# Output_v1_1.net
KiCad netlist of a schematic drawn in EAGLE
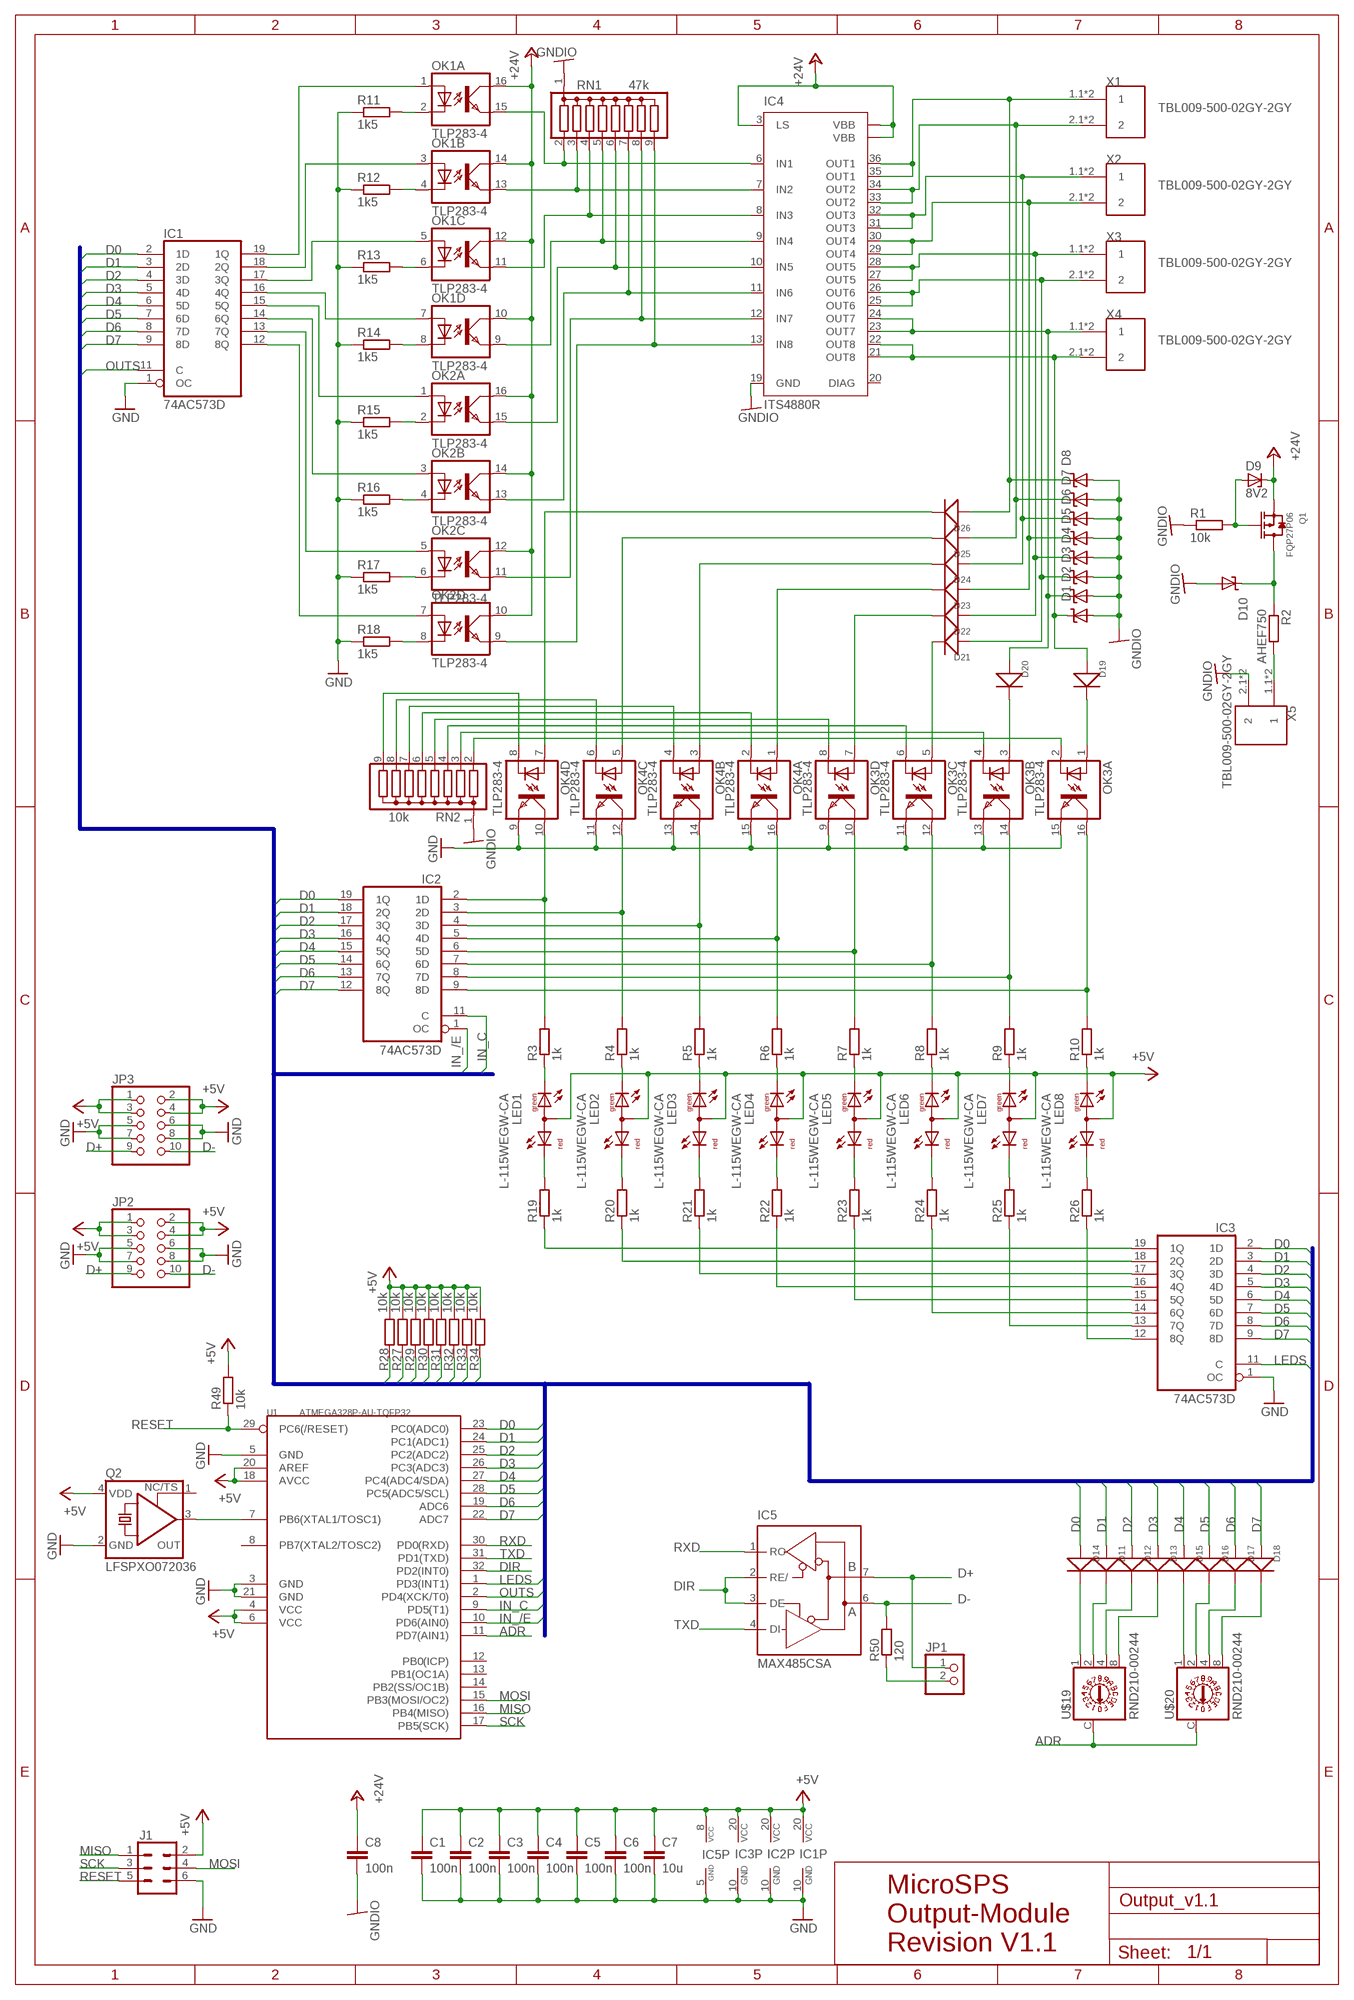
[diagram p0: schematic, sheet 1]

(export (version "E")
  (design (tool "Eeschema 10.0.6"))
  (components
    (comp (ref "C1")
      (value "100n")
      (footprint "eagle-import:C0805")
      (libsource (lib "eagle-import") (part "C-EUC0805"))
    )
    (comp (ref "C2")
      (value "100n")
      (footprint "eagle-import:C0805")
      (libsource (lib "eagle-import") (part "C-EUC0805"))
    )
    (comp (ref "C3")
      (value "100n")
      (footprint "eagle-import:C0805")
      (libsource (lib "eagle-import") (part "C-EUC0805"))
    )
    (comp (ref "C4")
      (value "100n")
      (footprint "eagle-import:C0805")
      (libsource (lib "eagle-import") (part "C-EUC0805"))
    )
    (comp (ref "C5")
      (value "100n")
      (footprint "eagle-import:C0805")
      (libsource (lib "eagle-import") (part "C-EUC0805"))
    )
    (comp (ref "C6")
      (value "100n")
      (footprint "eagle-import:C0805")
      (libsource (lib "eagle-import") (part "C-EUC0805"))
    )
    (comp (ref "C7")
      (value "10u")
      (footprint "eagle-import:C0805")
      (libsource (lib "eagle-import") (part "C-EUC0805"))
    )
    (comp (ref "C8")
      (value "100n")
      (footprint "eagle-import:C0805")
      (libsource (lib "eagle-import") (part "C-EUC0805"))
    )
    (comp (ref "D1")
      (value "SUPPRESSOR-SMBJ")
      (footprint "eagle-import:SMBJ")
      (libsource (lib "eagle-import") (part "SUPPRESSOR-SMBJ"))
    )
    (comp (ref "D2")
      (value "SUPPRESSOR-SMBJ")
      (footprint "eagle-import:SMBJ")
      (libsource (lib "eagle-import") (part "SUPPRESSOR-SMBJ"))
    )
    (comp (ref "D3")
      (value "SUPPRESSOR-SMBJ")
      (footprint "eagle-import:SMBJ")
      (libsource (lib "eagle-import") (part "SUPPRESSOR-SMBJ"))
    )
    (comp (ref "D4")
      (value "SUPPRESSOR-SMBJ")
      (footprint "eagle-import:SMBJ")
      (libsource (lib "eagle-import") (part "SUPPRESSOR-SMBJ"))
    )
    (comp (ref "D5")
      (value "SUPPRESSOR-SMBJ")
      (footprint "eagle-import:SMBJ")
      (libsource (lib "eagle-import") (part "SUPPRESSOR-SMBJ"))
    )
    (comp (ref "D6")
      (value "SUPPRESSOR-SMBJ")
      (footprint "eagle-import:SMBJ")
      (libsource (lib "eagle-import") (part "SUPPRESSOR-SMBJ"))
    )
    (comp (ref "D7")
      (value "SUPPRESSOR-SMBJ")
      (footprint "eagle-import:SMBJ")
      (libsource (lib "eagle-import") (part "SUPPRESSOR-SMBJ"))
    )
    (comp (ref "D8")
      (value "SUPPRESSOR-SMBJ")
      (footprint "eagle-import:SMBJ")
      (libsource (lib "eagle-import") (part "SUPPRESSOR-SMBJ"))
    )
    (comp (ref "D9")
      (value "8V2")
      (footprint "eagle-import:SOD80C")
      (libsource (lib "eagle-import") (part "ZENER-DIODESOD80C"))
    )
    (comp (ref "D10")
      (value "SUPPRESSOR-SMBJ")
      (footprint "eagle-import:SMBJ")
      (libsource (lib "eagle-import") (part "SUPPRESSOR-SMBJ"))
    )
    (comp (ref "D11")
      (value "DIODE'1N4148-SMD'")
      (footprint "eagle-import:LL-34")
      (libsource (lib "eagle-import") (part "DIODE'1N4148-SMD'"))
    )
    (comp (ref "D12")
      (value "DIODE'1N4148-SMD'")
      (footprint "eagle-import:LL-34")
      (libsource (lib "eagle-import") (part "DIODE'1N4148-SMD'"))
    )
    (comp (ref "D13")
      (value "DIODE'1N4148-SMD'")
      (footprint "eagle-import:LL-34")
      (libsource (lib "eagle-import") (part "DIODE'1N4148-SMD'"))
    )
    (comp (ref "D14")
      (value "DIODE'1N4148-SMD'")
      (footprint "eagle-import:LL-34")
      (libsource (lib "eagle-import") (part "DIODE'1N4148-SMD'"))
    )
    (comp (ref "D15")
      (value "DIODE'1N4148-SMD'")
      (footprint "eagle-import:LL-34")
      (libsource (lib "eagle-import") (part "DIODE'1N4148-SMD'"))
    )
    (comp (ref "D16")
      (value "DIODE'1N4148-SMD'")
      (footprint "eagle-import:LL-34")
      (libsource (lib "eagle-import") (part "DIODE'1N4148-SMD'"))
    )
    (comp (ref "D17")
      (value "DIODE'1N4148-SMD'")
      (footprint "eagle-import:LL-34")
      (libsource (lib "eagle-import") (part "DIODE'1N4148-SMD'"))
    )
    (comp (ref "D18")
      (value "DIODE'1N4148-SMD'")
      (footprint "eagle-import:LL-34")
      (libsource (lib "eagle-import") (part "DIODE'1N4148-SMD'"))
    )
    (comp (ref "D19")
      (value "DIODE'1N4148-SMD'")
      (footprint "eagle-import:LL-34")
      (libsource (lib "eagle-import") (part "DIODE'1N4148-SMD'"))
    )
    (comp (ref "D20")
      (value "DIODE'1N4148-SMD'")
      (footprint "eagle-import:LL-34")
      (libsource (lib "eagle-import") (part "DIODE'1N4148-SMD'"))
    )
    (comp (ref "D21")
      (value "DIODE'1N4148-SMD'")
      (footprint "eagle-import:LL-34")
      (libsource (lib "eagle-import") (part "DIODE'1N4148-SMD'"))
    )
    (comp (ref "D22")
      (value "DIODE'1N4148-SMD'")
      (footprint "eagle-import:LL-34")
      (libsource (lib "eagle-import") (part "DIODE'1N4148-SMD'"))
    )
    (comp (ref "D23")
      (value "DIODE'1N4148-SMD'")
      (footprint "eagle-import:LL-34")
      (libsource (lib "eagle-import") (part "DIODE'1N4148-SMD'"))
    )
    (comp (ref "D24")
      (value "DIODE'1N4148-SMD'")
      (footprint "eagle-import:LL-34")
      (libsource (lib "eagle-import") (part "DIODE'1N4148-SMD'"))
    )
    (comp (ref "D25")
      (value "DIODE'1N4148-SMD'")
      (footprint "eagle-import:LL-34")
      (libsource (lib "eagle-import") (part "DIODE'1N4148-SMD'"))
    )
    (comp (ref "D26")
      (value "DIODE'1N4148-SMD'")
      (footprint "eagle-import:LL-34")
      (libsource (lib "eagle-import") (part "DIODE'1N4148-SMD'"))
    )
    (comp (ref "IC1")
      (value "74AC573D")
      (footprint "eagle-import:SO20W")
      (libsource (lib "eagle-import") (part "74573DAC"))
    )
    (comp (ref "IC2")
      (value "74AC573D")
      (footprint "eagle-import:SO20W")
      (libsource (lib "eagle-import") (part "74573DAC"))
    )
    (comp (ref "IC3")
      (value "74AC573D")
      (footprint "eagle-import:SO20W")
      (libsource (lib "eagle-import") (part "74573DAC"))
    )
    (comp (ref "IC4")
      (value "ITS4880R")
      (footprint "eagle-import:PG-DSO-36")
      (libsource (lib "eagle-import") (part "ITS4880R"))
    )
    (comp (ref "IC5")
      (value "MAX485CSA")
      (footprint "eagle-import:SO08")
      (fields (field (name "MF") "MAXIM") (field (name "MPN") "MAX481CSA"))
      (libsource (lib "eagle-import") (part "MAX481CSA"))
    )
    (comp (ref "J1")
      (value "CONN_03X2FEMALE_SMD")
      (footprint "eagle-import:2X3_SMD")
      (libsource (lib "eagle-import") (part "CONN_03X2FEMALE_SMD"))
    )
    (comp (ref "JP1")
      (value "PINHD-1X2")
      (footprint "eagle-import:1X02")
      (libsource (lib "eagle-import") (part "PINHD-1X2"))
    )
    (comp (ref "JP2")
      (value "PINHD-2X5/90")
      (footprint "eagle-import:2X05_90")
      (libsource (lib "eagle-import") (part "PINHD-2X5/90"))
    )
    (comp (ref "JP3")
      (value "PINHD-2X5/90")
      (footprint "eagle-import:2X05_90")
      (libsource (lib "eagle-import") (part "PINHD-2X5/90"))
    )
    (comp (ref "LED1")
      (value "L-115WEGW-CA")
      (footprint "eagle-import:DUOLED-A-3MM")
      (libsource (lib "eagle-import") (part "L-115WEGW-CA"))
    )
    (comp (ref "LED2")
      (value "L-115WEGW-CA")
      (footprint "eagle-import:DUOLED-A-3MM")
      (libsource (lib "eagle-import") (part "L-115WEGW-CA"))
    )
    (comp (ref "LED3")
      (value "L-115WEGW-CA")
      (footprint "eagle-import:DUOLED-A-3MM")
      (libsource (lib "eagle-import") (part "L-115WEGW-CA"))
    )
    (comp (ref "LED4")
      (value "L-115WEGW-CA")
      (footprint "eagle-import:DUOLED-A-3MM")
      (libsource (lib "eagle-import") (part "L-115WEGW-CA"))
    )
    (comp (ref "LED5")
      (value "L-115WEGW-CA")
      (footprint "eagle-import:DUOLED-A-3MM")
      (libsource (lib "eagle-import") (part "L-115WEGW-CA"))
    )
    (comp (ref "LED6")
      (value "L-115WEGW-CA")
      (footprint "eagle-import:DUOLED-A-3MM")
      (libsource (lib "eagle-import") (part "L-115WEGW-CA"))
    )
    (comp (ref "LED7")
      (value "L-115WEGW-CA")
      (footprint "eagle-import:DUOLED-A-3MM")
      (libsource (lib "eagle-import") (part "L-115WEGW-CA"))
    )
    (comp (ref "LED8")
      (value "L-115WEGW-CA")
      (footprint "eagle-import:DUOLED-A-3MM")
      (libsource (lib "eagle-import") (part "L-115WEGW-CA"))
    )
    (comp (ref "OK1")
      (value "TLP283-4")
      (footprint "eagle-import:MINI-FLAT-16")
      (libsource (lib "eagle-import") (part "TLP283-4"))
    )
    (comp (ref "OK2")
      (value "TLP283-4")
      (footprint "eagle-import:MINI-FLAT-16")
      (libsource (lib "eagle-import") (part "TLP283-4"))
    )
    (comp (ref "OK3")
      (value "TLP283-4")
      (footprint "eagle-import:MINI-FLAT-16")
      (libsource (lib "eagle-import") (part "TLP283-4"))
    )
    (comp (ref "OK4")
      (value "TLP283-4")
      (footprint "eagle-import:MINI-FLAT-16")
      (libsource (lib "eagle-import") (part "TLP283-4"))
    )
    (comp (ref "Q1")
      (value "FQP27P06")
      (footprint "eagle-import:TO-220V")
      (libsource (lib "eagle-import") (part "DIP-MOSFET-P-CH-60V-27A-FQP27P06(TO-220)TO-220V"))
    )
    (comp (ref "Q2")
      (value "LFSPXO072036")
      (footprint "eagle-import:5.0X3.2_KXO-56")
      (libsource (lib "eagle-import") (part "KXO-PXO/XO-56-56"))
    )
    (comp (ref "R1")
      (value "10k")
      (footprint "eagle-import:R0805")
      (libsource (lib "eagle-import") (part "R-EU_R0805"))
    )
    (comp (ref "R2")
      (value "AHEF750")
      (footprint "eagle-import:0204_7")
      (libsource (lib "eagle-import") (part "resistor_R-EU_0204/7"))
    )
    (comp (ref "R3")
      (value "1k")
      (footprint "eagle-import:R0805")
      (libsource (lib "eagle-import") (part "R-EU_R0805"))
    )
    (comp (ref "R4")
      (value "1k")
      (footprint "eagle-import:R0805")
      (libsource (lib "eagle-import") (part "R-EU_R0805"))
    )
    (comp (ref "R5")
      (value "1k")
      (footprint "eagle-import:R0805")
      (libsource (lib "eagle-import") (part "R-EU_R0805"))
    )
    (comp (ref "R6")
      (value "1k")
      (footprint "eagle-import:R0805")
      (libsource (lib "eagle-import") (part "R-EU_R0805"))
    )
    (comp (ref "R7")
      (value "1k")
      (footprint "eagle-import:R0805")
      (libsource (lib "eagle-import") (part "R-EU_R0805"))
    )
    (comp (ref "R8")
      (value "1k")
      (footprint "eagle-import:R0805")
      (libsource (lib "eagle-import") (part "R-EU_R0805"))
    )
    (comp (ref "R9")
      (value "1k")
      (footprint "eagle-import:R0805")
      (libsource (lib "eagle-import") (part "R-EU_R0805"))
    )
    (comp (ref "R10")
      (value "1k")
      (footprint "eagle-import:R0805")
      (libsource (lib "eagle-import") (part "R-EU_R0805"))
    )
    (comp (ref "R11")
      (value "1k5")
      (footprint "eagle-import:R0805")
      (libsource (lib "eagle-import") (part "R-EU_R0805"))
    )
    (comp (ref "R12")
      (value "1k5")
      (footprint "eagle-import:R0805")
      (libsource (lib "eagle-import") (part "R-EU_R0805"))
    )
    (comp (ref "R13")
      (value "1k5")
      (footprint "eagle-import:R0805")
      (libsource (lib "eagle-import") (part "R-EU_R0805"))
    )
    (comp (ref "R14")
      (value "1k5")
      (footprint "eagle-import:R0805")
      (libsource (lib "eagle-import") (part "R-EU_R0805"))
    )
    (comp (ref "R15")
      (value "1k5")
      (footprint "eagle-import:R0805")
      (libsource (lib "eagle-import") (part "R-EU_R0805"))
    )
    (comp (ref "R16")
      (value "1k5")
      (footprint "eagle-import:R0805")
      (libsource (lib "eagle-import") (part "R-EU_R0805"))
    )
    (comp (ref "R17")
      (value "1k5")
      (footprint "eagle-import:R0805")
      (libsource (lib "eagle-import") (part "R-EU_R0805"))
    )
    (comp (ref "R18")
      (value "1k5")
      (footprint "eagle-import:R0805")
      (libsource (lib "eagle-import") (part "R-EU_R0805"))
    )
    (comp (ref "R19")
      (value "1k")
      (footprint "eagle-import:R0805")
      (libsource (lib "eagle-import") (part "R-EU_R0805"))
    )
    (comp (ref "R20")
      (value "1k")
      (footprint "eagle-import:R0805")
      (libsource (lib "eagle-import") (part "R-EU_R0805"))
    )
    (comp (ref "R21")
      (value "1k")
      (footprint "eagle-import:R0805")
      (libsource (lib "eagle-import") (part "R-EU_R0805"))
    )
    (comp (ref "R22")
      (value "1k")
      (footprint "eagle-import:R0805")
      (libsource (lib "eagle-import") (part "R-EU_R0805"))
    )
    (comp (ref "R23")
      (value "1k")
      (footprint "eagle-import:R0805")
      (libsource (lib "eagle-import") (part "R-EU_R0805"))
    )
    (comp (ref "R24")
      (value "1k")
      (footprint "eagle-import:R0805")
      (libsource (lib "eagle-import") (part "R-EU_R0805"))
    )
    (comp (ref "R25")
      (value "1k")
      (footprint "eagle-import:R0805")
      (libsource (lib "eagle-import") (part "R-EU_R0805"))
    )
    (comp (ref "R26")
      (value "1k")
      (footprint "eagle-import:R0805")
      (libsource (lib "eagle-import") (part "R-EU_R0805"))
    )
    (comp (ref "R27")
      (value "10k")
      (footprint "eagle-import:R0805")
      (libsource (lib "eagle-import") (part "R-EU_R0805"))
    )
    (comp (ref "R28")
      (value "10k")
      (footprint "eagle-import:R0805")
      (libsource (lib "eagle-import") (part "R-EU_R0805"))
    )
    (comp (ref "R29")
      (value "10k")
      (footprint "eagle-import:R0805")
      (libsource (lib "eagle-import") (part "R-EU_R0805"))
    )
    (comp (ref "R30")
      (value "10k")
      (footprint "eagle-import:R0805")
      (libsource (lib "eagle-import") (part "R-EU_R0805"))
    )
    (comp (ref "R31")
      (value "10k")
      (footprint "eagle-import:R0805")
      (libsource (lib "eagle-import") (part "R-EU_R0805"))
    )
    (comp (ref "R32")
      (value "10k")
      (footprint "eagle-import:R0805")
      (libsource (lib "eagle-import") (part "R-EU_R0805"))
    )
    (comp (ref "R33")
      (value "10k")
      (footprint "eagle-import:R0805")
      (libsource (lib "eagle-import") (part "R-EU_R0805"))
    )
    (comp (ref "R34")
      (value "10k")
      (footprint "eagle-import:R0805")
      (libsource (lib "eagle-import") (part "R-EU_R0805"))
    )
    (comp (ref "R49")
      (value "10k")
      (footprint "eagle-import:R0805")
      (libsource (lib "eagle-import") (part "R-EU_R0805"))
    )
    (comp (ref "R50")
      (value "120")
      (footprint "eagle-import:R0805")
      (libsource (lib "eagle-import") (part "R-EU_R0805"))
    )
    (comp (ref "RN1")
      (value "47k")
      (footprint "eagle-import:SIL9")
      (libsource (lib "eagle-import") (part "G08R"))
    )
    (comp (ref "RN2")
      (value "10k")
      (footprint "eagle-import:SIL9")
      (libsource (lib "eagle-import") (part "G08R"))
    )
    (comp (ref "U$19")
      (value "RND210-00244")
      (footprint "eagle-import:RND210-00244")
      (libsource (lib "eagle-import") (part "RND210-00244"))
    )
    (comp (ref "U$20")
      (value "RND210-00244")
      (footprint "eagle-import:RND210-00244")
      (libsource (lib "eagle-import") (part "RND210-00244"))
    )
    (comp (ref "U1")
      (value "ATMEGA328P-AU-TQFP32")
      (footprint "eagle-import:TQFP32-0.8-7X7MM")
      (fields (field (name "MPN") "ATMEGA328P-AU"))
      (libsource (lib "eagle-import") (part "MCU-ATMEGA328P-AU(TQFP32)"))
    )
    (comp (ref "X1")
      (value "TBL009-500-02GY-2GY")
      (footprint "eagle-import:TBL009-500-02GY-2GY")
      (libsource (lib "eagle-import") (part "TBL009-500-02GY-2GY"))
    )
    (comp (ref "X2")
      (value "TBL009-500-02GY-2GY")
      (footprint "eagle-import:TBL009-500-02GY-2GY")
      (libsource (lib "eagle-import") (part "TBL009-500-02GY-2GY"))
    )
    (comp (ref "X3")
      (value "TBL009-500-02GY-2GY")
      (footprint "eagle-import:TBL009-500-02GY-2GY")
      (libsource (lib "eagle-import") (part "TBL009-500-02GY-2GY"))
    )
    (comp (ref "X4")
      (value "TBL009-500-02GY-2GY")
      (footprint "eagle-import:TBL009-500-02GY-2GY")
      (libsource (lib "eagle-import") (part "TBL009-500-02GY-2GY"))
    )
    (comp (ref "X5")
      (value "TBL009-500-02GY-2GY")
      (footprint "eagle-import:TBL009-500-02GY-2GY")
      (libsource (lib "eagle-import") (part "TBL009-500-02GY-2GY"))
    )
  )
  (nets
    (net (code "1") (name "+5V") (class "Default")
      (node (ref "C1") (pin "1") (pinfunction "1_1") (pintype "passive"))
      (node (ref "C2") (pin "1") (pinfunction "1_1") (pintype "passive"))
      (node (ref "C3") (pin "1") (pinfunction "1_1") (pintype "passive"))
      (node (ref "C4") (pin "1") (pinfunction "1_1") (pintype "passive"))
      (node (ref "C5") (pin "1") (pinfunction "1_1") (pintype "passive"))
      (node (ref "C6") (pin "1") (pinfunction "1_1") (pintype "passive"))
      (node (ref "C7") (pin "1") (pinfunction "1_1") (pintype "passive"))
      (node (ref "IC1") (pin "20") (pinfunction "VCC_20") (pintype "power_in"))
      (node (ref "IC2") (pin "20") (pinfunction "VCC_20") (pintype "power_in"))
      (node (ref "IC3") (pin "20") (pinfunction "VCC_20") (pintype "power_in"))
      (node (ref "IC5") (pin "8") (pinfunction "VCC_8") (pintype "power_in"))
      (node (ref "J1") (pin "2") (pinfunction "2_2") (pintype "bidirectional"))
      (node (ref "JP2") (pin "1") (pinfunction "1_1") (pintype "passive"))
      (node (ref "JP2") (pin "2") (pinfunction "2_2") (pintype "passive"))
      (node (ref "JP2") (pin "3") (pinfunction "3_3") (pintype "passive"))
      (node (ref "JP2") (pin "4") (pinfunction "4_4") (pintype "passive"))
      (node (ref "JP3") (pin "1") (pinfunction "1_1") (pintype "passive"))
      (node (ref "JP3") (pin "2") (pinfunction "2_2") (pintype "passive"))
      (node (ref "JP3") (pin "3") (pinfunction "3_3") (pintype "passive"))
      (node (ref "JP3") (pin "4") (pinfunction "4_4") (pintype "passive"))
      (node (ref "LED1") (pin "2") (pinfunction "A_2") (pintype "passive"))
      (node (ref "LED2") (pin "2") (pinfunction "A_2") (pintype "passive"))
      (node (ref "LED3") (pin "2") (pinfunction "A_2") (pintype "passive"))
      (node (ref "LED4") (pin "2") (pinfunction "A_2") (pintype "passive"))
      (node (ref "LED5") (pin "2") (pinfunction "A_2") (pintype "passive"))
      (node (ref "LED6") (pin "2") (pinfunction "A_2") (pintype "passive"))
      (node (ref "LED7") (pin "2") (pinfunction "A_2") (pintype "passive"))
      (node (ref "LED8") (pin "2") (pinfunction "A_2") (pintype "passive"))
      (node (ref "Q2") (pin "4") (pinfunction "VDD_4") (pintype "power_in"))
      (node (ref "R27") (pin "2") (pinfunction "2_2") (pintype "passive"))
      (node (ref "R28") (pin "2") (pinfunction "2_2") (pintype "passive"))
      (node (ref "R29") (pin "2") (pinfunction "2_2") (pintype "passive"))
      (node (ref "R30") (pin "2") (pinfunction "2_2") (pintype "passive"))
      (node (ref "R31") (pin "2") (pinfunction "2_2") (pintype "passive"))
      (node (ref "R32") (pin "2") (pinfunction "2_2") (pintype "passive"))
      (node (ref "R33") (pin "2") (pinfunction "2_2") (pintype "passive"))
      (node (ref "R34") (pin "2") (pinfunction "2_2") (pintype "passive"))
      (node (ref "R49") (pin "2") (pinfunction "2_2") (pintype "passive"))
      (node (ref "U1") (pin "18") (pinfunction "AVCC_18") (pintype "bidirectional"))
      (node (ref "U1") (pin "20") (pinfunction "AREF_20") (pintype "bidirectional"))
      (node (ref "U1") (pin "4") (pinfunction "VCC_4") (pintype "bidirectional"))
      (node (ref "U1") (pin "6") (pinfunction "VCC_6") (pintype "bidirectional"))
    )
    (net (code "2") (name "+24V") (class "Default")
      (node (ref "C8") (pin "1") (pinfunction "1_1") (pintype "passive"))
      (node (ref "D9") (pin "C") (pinfunction "C_C") (pintype "passive"))
      (node (ref "IC4") (pin "3") (pinfunction "LS_3") (pintype "input"))
      (node (ref "IC4") (pin "TH@1") (pinfunction "VBB_TH@1") (pintype "input"))
      (node (ref "IC4") (pin "TH@2") (pinfunction "VBB_TH@2") (pintype "input"))
      (node (ref "OK1") (pin "10") (pinfunction "COL_10") (pintype "passive"))
      (node (ref "OK1") (pin "12") (pinfunction "COL_12") (pintype "passive"))
      (node (ref "OK1") (pin "14") (pinfunction "COL_14") (pintype "passive"))
      (node (ref "OK1") (pin "16") (pinfunction "COL_16") (pintype "passive"))
      (node (ref "OK2") (pin "10") (pinfunction "COL_10") (pintype "passive"))
      (node (ref "OK2") (pin "12") (pinfunction "COL_12") (pintype "passive"))
      (node (ref "OK2") (pin "14") (pinfunction "COL_14") (pintype "passive"))
      (node (ref "OK2") (pin "16") (pinfunction "COL_16") (pintype "passive"))
      (node (ref "Q1") (pin "3") (pinfunction "S_3") (pintype "passive"))
    )
    (net (code "3") (name "/ADR") (class "Default")
      (node (ref "U$19") (pin "C") (pinfunction "C_C") (pintype "passive"))
      (node (ref "U$20") (pin "C") (pinfunction "C_C") (pintype "passive"))
      (node (ref "U1") (pin "11") (pinfunction "PD7(AIN1)_11") (pintype "bidirectional"))
    )
    (net (code "4") (name "/D+") (class "Default")
      (node (ref "IC5") (pin "7") (pinfunction "B_7") (pintype "passive"))
      (node (ref "JP1") (pin "1") (pinfunction "1_1") (pintype "passive"))
      (node (ref "JP2") (pin "9") (pinfunction "9_9") (pintype "passive"))
      (node (ref "JP3") (pin "9") (pinfunction "9_9") (pintype "passive"))
    )
    (net (code "5") (name "/D-") (class "Default")
      (node (ref "IC5") (pin "6") (pinfunction "A_6") (pintype "passive"))
      (node (ref "JP2") (pin "10") (pinfunction "10_10") (pintype "passive"))
      (node (ref "JP3") (pin "10") (pinfunction "10_10") (pintype "passive"))
      (node (ref "R50") (pin "2") (pinfunction "2_2") (pintype "passive"))
    )
    (net (code "6") (name "/D0") (class "Default")
      (node (ref "D14") (pin "A") (pinfunction "+_A") (pintype "passive"))
      (node (ref "IC1") (pin "2") (pinfunction "1D_2") (pintype "input"))
      (node (ref "IC2") (pin "19") (pinfunction "1Q_19") (pintype "tri_state"))
      (node (ref "IC3") (pin "2") (pinfunction "1D_2") (pintype "input"))
      (node (ref "R28") (pin "1") (pinfunction "1_1") (pintype "passive"))
      (node (ref "U1") (pin "23") (pinfunction "PC0(ADC0)_23") (pintype "bidirectional"))
    )
    (net (code "7") (name "/D1") (class "Default")
      (node (ref "D11") (pin "A") (pinfunction "+_A") (pintype "passive"))
      (node (ref "IC1") (pin "3") (pinfunction "2D_3") (pintype "input"))
      (node (ref "IC2") (pin "18") (pinfunction "2Q_18") (pintype "tri_state"))
      (node (ref "IC3") (pin "3") (pinfunction "2D_3") (pintype "input"))
      (node (ref "R27") (pin "1") (pinfunction "1_1") (pintype "passive"))
      (node (ref "U1") (pin "24") (pinfunction "PC1(ADC1)_24") (pintype "bidirectional"))
    )
    (net (code "8") (name "/D2") (class "Default")
      (node (ref "D12") (pin "A") (pinfunction "+_A") (pintype "passive"))
      (node (ref "IC1") (pin "4") (pinfunction "3D_4") (pintype "input"))
      (node (ref "IC2") (pin "17") (pinfunction "3Q_17") (pintype "tri_state"))
      (node (ref "IC3") (pin "4") (pinfunction "3D_4") (pintype "input"))
      (node (ref "R29") (pin "1") (pinfunction "1_1") (pintype "passive"))
      (node (ref "U1") (pin "25") (pinfunction "PC2(ADC2)_25") (pintype "bidirectional"))
    )
    (net (code "9") (name "/D3") (class "Default")
      (node (ref "D13") (pin "A") (pinfunction "+_A") (pintype "passive"))
      (node (ref "IC1") (pin "5") (pinfunction "4D_5") (pintype "input"))
      (node (ref "IC2") (pin "16") (pinfunction "4Q_16") (pintype "tri_state"))
      (node (ref "IC3") (pin "5") (pinfunction "4D_5") (pintype "input"))
      (node (ref "R30") (pin "1") (pinfunction "1_1") (pintype "passive"))
      (node (ref "U1") (pin "26") (pinfunction "PC3(ADC3)_26") (pintype "bidirectional"))
    )
    (net (code "10") (name "/D4") (class "Default")
      (node (ref "D15") (pin "A") (pinfunction "+_A") (pintype "passive"))
      (node (ref "IC1") (pin "6") (pinfunction "5D_6") (pintype "input"))
      (node (ref "IC2") (pin "15") (pinfunction "5Q_15") (pintype "tri_state"))
      (node (ref "IC3") (pin "6") (pinfunction "5D_6") (pintype "input"))
      (node (ref "R31") (pin "1") (pinfunction "1_1") (pintype "passive"))
      (node (ref "U1") (pin "27") (pinfunction "PC4(ADC4/SDA)_27") (pintype "bidirectional"))
    )
    (net (code "11") (name "/D5") (class "Default")
      (node (ref "D16") (pin "A") (pinfunction "+_A") (pintype "passive"))
      (node (ref "IC1") (pin "7") (pinfunction "6D_7") (pintype "input"))
      (node (ref "IC2") (pin "14") (pinfunction "6Q_14") (pintype "tri_state"))
      (node (ref "IC3") (pin "7") (pinfunction "6D_7") (pintype "input"))
      (node (ref "R32") (pin "1") (pinfunction "1_1") (pintype "passive"))
      (node (ref "U1") (pin "28") (pinfunction "PC5(ADC5/SCL)_28") (pintype "bidirectional"))
    )
    (net (code "12") (name "/D6") (class "Default")
      (node (ref "D17") (pin "A") (pinfunction "+_A") (pintype "passive"))
      (node (ref "IC1") (pin "8") (pinfunction "7D_8") (pintype "input"))
      (node (ref "IC2") (pin "13") (pinfunction "7Q_13") (pintype "tri_state"))
      (node (ref "IC3") (pin "8") (pinfunction "7D_8") (pintype "input"))
      (node (ref "R33") (pin "1") (pinfunction "1_1") (pintype "passive"))
      (node (ref "U1") (pin "19") (pinfunction "ADC6_19") (pintype "bidirectional"))
    )
    (net (code "13") (name "/D7") (class "Default")
      (node (ref "D18") (pin "A") (pinfunction "+_A") (pintype "passive"))
      (node (ref "IC1") (pin "9") (pinfunction "8D_9") (pintype "input"))
      (node (ref "IC2") (pin "12") (pinfunction "8Q_12") (pintype "tri_state"))
      (node (ref "IC3") (pin "9") (pinfunction "8D_9") (pintype "input"))
      (node (ref "R34") (pin "1") (pinfunction "1_1") (pintype "passive"))
      (node (ref "U1") (pin "22") (pinfunction "ADC7_22") (pintype "bidirectional"))
    )
    (net (code "14") (name "/DIR") (class "Default")
      (node (ref "IC5") (pin "2") (pinfunction "RE/_2") (pintype "input"))
      (node (ref "IC5") (pin "3") (pinfunction "DE_3") (pintype "input"))
      (node (ref "U1") (pin "32") (pinfunction "PD2(INT0)_32") (pintype "bidirectional"))
    )
    (net (code "15") (name "/IN_C") (class "Default")
      (node (ref "IC2") (pin "11") (pinfunction "C_11") (pintype "input"))
      (node (ref "U1") (pin "9") (pinfunction "PD5(T1)_9") (pintype "bidirectional"))
    )
    (net (code "16") (name "/IN_{slash}E") (class "Default")
      (node (ref "IC2") (pin "1") (pinfunction "OC_1") (pintype "input"))
      (node (ref "U1") (pin "10") (pinfunction "PD6(AIN0)_10") (pintype "bidirectional"))
    )
    (net (code "17") (name "/LEDS") (class "Default")
      (node (ref "IC3") (pin "11") (pinfunction "C_11") (pintype "input"))
      (node (ref "U1") (pin "1") (pinfunction "PD3(INT1)_1") (pintype "bidirectional"))
    )
    (net (code "18") (name "/MISO") (class "Default")
      (node (ref "J1") (pin "1") (pinfunction "1_1") (pintype "bidirectional"))
      (node (ref "U1") (pin "16") (pinfunction "PB4(MISO)_16") (pintype "bidirectional"))
    )
    (net (code "19") (name "/MOSI") (class "Default")
      (node (ref "J1") (pin "4") (pinfunction "4_4") (pintype "bidirectional"))
      (node (ref "U1") (pin "15") (pinfunction "PB3(MOSI/OC2)_15") (pintype "bidirectional"))
    )
    (net (code "20") (name "/OUTS") (class "Default")
      (node (ref "IC1") (pin "11") (pinfunction "C_11") (pintype "input"))
      (node (ref "U1") (pin "2") (pinfunction "PD4(XCK/T0)_2") (pintype "bidirectional"))
    )
    (net (code "21") (name "/RESET") (class "Default")
      (node (ref "J1") (pin "5") (pinfunction "5_5") (pintype "bidirectional"))
      (node (ref "R49") (pin "1") (pinfunction "1_1") (pintype "passive"))
      (node (ref "U1") (pin "29") (pinfunction "PC6(/RESET)_29") (pintype "bidirectional"))
    )
    (net (code "22") (name "/RXD") (class "Default")
      (node (ref "IC5") (pin "1") (pinfunction "RO_1") (pintype "output"))
      (node (ref "U1") (pin "30") (pinfunction "PD0(RXD)_30") (pintype "bidirectional"))
    )
    (net (code "23") (name "/SCK") (class "Default")
      (node (ref "J1") (pin "3") (pinfunction "3_3") (pintype "bidirectional"))
      (node (ref "U1") (pin "17") (pinfunction "PB5(SCK)_17") (pintype "bidirectional"))
    )
    (net (code "24") (name "/TXD") (class "Default")
      (node (ref "IC5") (pin "4") (pinfunction "DI_4") (pintype "input"))
      (node (ref "U1") (pin "31") (pinfunction "PD1(TXD)_31") (pintype "bidirectional"))
    )
    (net (code "25") (name "GND") (class "Default")
      (node (ref "C1") (pin "2") (pinfunction "2_2") (pintype "passive"))
      (node (ref "C2") (pin "2") (pinfunction "2_2") (pintype "passive"))
      (node (ref "C3") (pin "2") (pinfunction "2_2") (pintype "passive"))
      (node (ref "C4") (pin "2") (pinfunction "2_2") (pintype "passive"))
      (node (ref "C5") (pin "2") (pinfunction "2_2") (pintype "passive"))
      (node (ref "C6") (pin "2") (pinfunction "2_2") (pintype "passive"))
      (node (ref "C7") (pin "2") (pinfunction "2_2") (pintype "passive"))
      (node (ref "IC1") (pin "1") (pinfunction "OC_1") (pintype "input"))
      (node (ref "IC1") (pin "10") (pinfunction "GND_10") (pintype "power_in"))
      (node (ref "IC2") (pin "10") (pinfunction "GND_10") (pintype "power_in"))
      (node (ref "IC3") (pin "1") (pinfunction "OC_1") (pintype "input"))
      (node (ref "IC3") (pin "10") (pinfunction "GND_10") (pintype "power_in"))
      (node (ref "IC5") (pin "5") (pinfunction "GND_5") (pintype "power_in"))
      (node (ref "J1") (pin "6") (pinfunction "6_6") (pintype "bidirectional"))
      (node (ref "JP2") (pin "5") (pinfunction "5_5") (pintype "passive"))
      (node (ref "JP2") (pin "6") (pinfunction "6_6") (pintype "passive"))
      (node (ref "JP2") (pin "7") (pinfunction "7_7") (pintype "passive"))
      (node (ref "JP2") (pin "8") (pinfunction "8_8") (pintype "passive"))
      (node (ref "JP3") (pin "5") (pinfunction "5_5") (pintype "passive"))
      (node (ref "JP3") (pin "6") (pinfunction "6_6") (pintype "passive"))
      (node (ref "JP3") (pin "7") (pinfunction "7_7") (pintype "passive"))
      (node (ref "JP3") (pin "8") (pinfunction "8_8") (pintype "passive"))
      (node (ref "OK3") (pin "11") (pinfunction "EMIT_11") (pintype "passive"))
      (node (ref "OK3") (pin "13") (pinfunction "EMIT_13") (pintype "passive"))
      (node (ref "OK3") (pin "15") (pinfunction "EMIT_15") (pintype "passive"))
      (node (ref "OK3") (pin "9") (pinfunction "EMIT_9") (pintype "passive"))
      (node (ref "OK4") (pin "11") (pinfunction "EMIT_11") (pintype "passive"))
      (node (ref "OK4") (pin "13") (pinfunction "EMIT_13") (pintype "passive"))
      (node (ref "OK4") (pin "15") (pinfunction "EMIT_15") (pintype "passive"))
      (node (ref "OK4") (pin "9") (pinfunction "EMIT_9") (pintype "passive"))
      (node (ref "Q2") (pin "2") (pinfunction "GND_2") (pintype "power_in"))
      (node (ref "R11") (pin "1") (pinfunction "1_1") (pintype "passive"))
      (node (ref "R12") (pin "1") (pinfunction "1_1") (pintype "passive"))
      (node (ref "R13") (pin "1") (pinfunction "1_1") (pintype "passive"))
      (node (ref "R14") (pin "1") (pinfunction "1_1") (pintype "passive"))
      (node (ref "R15") (pin "1") (pinfunction "1_1") (pintype "passive"))
      (node (ref "R16") (pin "1") (pinfunction "1_1") (pintype "passive"))
      (node (ref "R17") (pin "1") (pinfunction "1_1") (pintype "passive"))
      (node (ref "R18") (pin "1") (pinfunction "1_1") (pintype "passive"))
      (node (ref "U1") (pin "21") (pinfunction "GND_21") (pintype "bidirectional"))
      (node (ref "U1") (pin "3") (pinfunction "GND_3") (pintype "bidirectional"))
      (node (ref "U1") (pin "5") (pinfunction "GND_5") (pintype "bidirectional"))
    )
    (net (code "26") (name "GNDIO") (class "Default")
      (node (ref "C8") (pin "2") (pinfunction "2_2") (pintype "passive"))
      (node (ref "D1") (pin "A") (pinfunction "A_A") (pintype "passive"))
      (node (ref "D10") (pin "A") (pinfunction "A_A") (pintype "passive"))
      (node (ref "D2") (pin "A") (pinfunction "A_A") (pintype "passive"))
      (node (ref "D3") (pin "A") (pinfunction "A_A") (pintype "passive"))
      (node (ref "D4") (pin "A") (pinfunction "A_A") (pintype "passive"))
      (node (ref "D5") (pin "A") (pinfunction "A_A") (pintype "passive"))
      (node (ref "D6") (pin "A") (pinfunction "A_A") (pintype "passive"))
      (node (ref "D7") (pin "A") (pinfunction "A_A") (pintype "passive"))
      (node (ref "D8") (pin "A") (pinfunction "A_A") (pintype "passive"))
      (node (ref "IC4") (pin "19") (pinfunction "GND_19") (pintype "power_in"))
      (node (ref "R1") (pin "1") (pinfunction "1_1") (pintype "passive"))
      (node (ref "RN1") (pin "1") (pinfunction "1_1") (pintype "passive"))
      (node (ref "RN2") (pin "1") (pinfunction "1_1") (pintype "passive"))
      (node (ref "X5") (pin "2.1") (pinfunction "2_2.1") (pintype "bidirectional"))
      (node (ref "X5") (pin "2.2") (pinfunction "2_2.2") (pintype "bidirectional"))
    )
    (net (code "27") (name "Net-(D11--)") (class "Default")
      (node (ref "D11") (pin "C") (pinfunction "-_C") (pintype "passive"))
      (node (ref "U$19") (pin "2") (pinfunction "2_2") (pintype "passive"))
    )
    (net (code "28") (name "Net-(D12--)") (class "Default")
      (node (ref "D12") (pin "C") (pinfunction "-_C") (pintype "passive"))
      (node (ref "U$19") (pin "4") (pinfunction "4_4") (pintype "passive"))
    )
    (net (code "29") (name "Net-(D13--)") (class "Default")
      (node (ref "D13") (pin "C") (pinfunction "-_C") (pintype "passive"))
      (node (ref "U$19") (pin "8") (pinfunction "8_8") (pintype "passive"))
    )
    (net (code "30") (name "Net-(D14--)") (class "Default")
      (node (ref "D14") (pin "C") (pinfunction "-_C") (pintype "passive"))
      (node (ref "U$19") (pin "1") (pinfunction "1_1") (pintype "passive"))
    )
    (net (code "31") (name "Net-(D15--)") (class "Default")
      (node (ref "D15") (pin "C") (pinfunction "-_C") (pintype "passive"))
      (node (ref "U$20") (pin "1") (pinfunction "1_1") (pintype "passive"))
    )
    (net (code "32") (name "Net-(D16--)") (class "Default")
      (node (ref "D16") (pin "C") (pinfunction "-_C") (pintype "passive"))
      (node (ref "U$20") (pin "2") (pinfunction "2_2") (pintype "passive"))
    )
    (net (code "33") (name "Net-(D17--)") (class "Default")
      (node (ref "D17") (pin "C") (pinfunction "-_C") (pintype "passive"))
      (node (ref "U$20") (pin "4") (pinfunction "4_4") (pintype "passive"))
    )
    (net (code "34") (name "Net-(D18--)") (class "Default")
      (node (ref "D18") (pin "C") (pinfunction "-_C") (pintype "passive"))
      (node (ref "U$20") (pin "8") (pinfunction "8_8") (pintype "passive"))
    )
    (net (code "35") (name "Net-(D19-+)") (class "Default")
      (node (ref "D1") (pin "C") (pinfunction "C_C") (pintype "passive"))
      (node (ref "D19") (pin "A") (pinfunction "+_A") (pintype "passive"))
      (node (ref "IC4") (pin "21") (pinfunction "OUT8_21") (pintype "output"))
      (node (ref "IC4") (pin "22") (pinfunction "OUT8_22") (pintype "output"))
      (node (ref "X4") (pin "2.1") (pinfunction "2_2.1") (pintype "bidirectional"))
      (node (ref "X4") (pin "2.2") (pinfunction "2_2.2") (pintype "bidirectional"))
    )
    (net (code "36") (name "Net-(D19--)") (class "Default")
      (node (ref "D19") (pin "C") (pinfunction "-_C") (pintype "passive"))
      (node (ref "OK3") (pin "1") (pinfunction "A_1") (pintype "passive"))
    )
    (net (code "37") (name "Net-(D20-+)") (class "Default")
      (node (ref "D2") (pin "C") (pinfunction "C_C") (pintype "passive"))
      (node (ref "D20") (pin "A") (pinfunction "+_A") (pintype "passive"))
      (node (ref "IC4") (pin "23") (pinfunction "OUT7_23") (pintype "output"))
      (node (ref "IC4") (pin "24") (pinfunction "OUT7_24") (pintype "output"))
      (node (ref "X4") (pin "1.1") (pinfunction "1_1.1") (pintype "bidirectional"))
      (node (ref "X4") (pin "1.2") (pinfunction "1_1.2") (pintype "bidirectional"))
    )
    (net (code "38") (name "Net-(D20--)") (class "Default")
      (node (ref "D20") (pin "C") (pinfunction "-_C") (pintype "passive"))
      (node (ref "OK3") (pin "3") (pinfunction "A_3") (pintype "passive"))
    )
    (net (code "39") (name "Net-(D21-+)") (class "Default")
      (node (ref "D21") (pin "A") (pinfunction "+_A") (pintype "passive"))
      (node (ref "D3") (pin "C") (pinfunction "C_C") (pintype "passive"))
      (node (ref "IC4") (pin "25") (pinfunction "OUT6_25") (pintype "output"))
      (node (ref "IC4") (pin "26") (pinfunction "OUT6_26") (pintype "output"))
      (node (ref "X3") (pin "2.1") (pinfunction "2_2.1") (pintype "bidirectional"))
      (node (ref "X3") (pin "2.2") (pinfunction "2_2.2") (pintype "bidirectional"))
    )
    (net (code "40") (name "Net-(D21--)") (class "Default")
      (node (ref "D21") (pin "C") (pinfunction "-_C") (pintype "passive"))
      (node (ref "OK3") (pin "5") (pinfunction "A_5") (pintype "passive"))
    )
    (net (code "41") (name "Net-(D22-+)") (class "Default")
      (node (ref "D22") (pin "A") (pinfunction "+_A") (pintype "passive"))
      (node (ref "D4") (pin "C") (pinfunction "C_C") (pintype "passive"))
      (node (ref "IC4") (pin "27") (pinfunction "OUT5_27") (pintype "output"))
      (node (ref "IC4") (pin "28") (pinfunction "OUT5_28") (pintype "output"))
      (node (ref "X3") (pin "1.1") (pinfunction "1_1.1") (pintype "bidirectional"))
      (node (ref "X3") (pin "1.2") (pinfunction "1_1.2") (pintype "bidirectional"))
    )
    (net (code "42") (name "Net-(D22--)") (class "Default")
      (node (ref "D22") (pin "C") (pinfunction "-_C") (pintype "passive"))
      (node (ref "OK3") (pin "7") (pinfunction "A_7") (pintype "passive"))
    )
    (net (code "43") (name "Net-(D23-+)") (class "Default")
      (node (ref "D23") (pin "A") (pinfunction "+_A") (pintype "passive"))
      (node (ref "D5") (pin "C") (pinfunction "C_C") (pintype "passive"))
      (node (ref "IC4") (pin "29") (pinfunction "OUT4_29") (pintype "output"))
      (node (ref "IC4") (pin "30") (pinfunction "OUT4_30") (pintype "output"))
      (node (ref "X2") (pin "2.1") (pinfunction "2_2.1") (pintype "bidirectional"))
      (node (ref "X2") (pin "2.2") (pinfunction "2_2.2") (pintype "bidirectional"))
    )
    (net (code "44") (name "Net-(D23--)") (class "Default")
      (node (ref "D23") (pin "C") (pinfunction "-_C") (pintype "passive"))
      (node (ref "OK4") (pin "1") (pinfunction "A_1") (pintype "passive"))
    )
    (net (code "45") (name "Net-(D24-+)") (class "Default")
      (node (ref "D24") (pin "A") (pinfunction "+_A") (pintype "passive"))
      (node (ref "D6") (pin "C") (pinfunction "C_C") (pintype "passive"))
      (node (ref "IC4") (pin "31") (pinfunction "OUT3_31") (pintype "output"))
      (node (ref "IC4") (pin "32") (pinfunction "OUT3_32") (pintype "output"))
      (node (ref "X2") (pin "1.1") (pinfunction "1_1.1") (pintype "bidirectional"))
      (node (ref "X2") (pin "1.2") (pinfunction "1_1.2") (pintype "bidirectional"))
    )
    (net (code "46") (name "Net-(D24--)") (class "Default")
      (node (ref "D24") (pin "C") (pinfunction "-_C") (pintype "passive"))
      (node (ref "OK4") (pin "3") (pinfunction "A_3") (pintype "passive"))
    )
    (net (code "47") (name "Net-(D25-+)") (class "Default")
      (node (ref "D25") (pin "A") (pinfunction "+_A") (pintype "passive"))
      (node (ref "D7") (pin "C") (pinfunction "C_C") (pintype "passive"))
      (node (ref "IC4") (pin "33") (pinfunction "OUT2_33") (pintype "output"))
      (node (ref "IC4") (pin "34") (pinfunction "OUT2_34") (pintype "output"))
      (node (ref "X1") (pin "2.1") (pinfunction "2_2.1") (pintype "bidirectional"))
      (node (ref "X1") (pin "2.2") (pinfunction "2_2.2") (pintype "bidirectional"))
    )
    (net (code "48") (name "Net-(D25--)") (class "Default")
      (node (ref "D25") (pin "C") (pinfunction "-_C") (pintype "passive"))
      (node (ref "OK4") (pin "5") (pinfunction "A_5") (pintype "passive"))
    )
    (net (code "49") (name "Net-(D26-+)") (class "Default")
      (node (ref "D26") (pin "A") (pinfunction "+_A") (pintype "passive"))
      (node (ref "D8") (pin "C") (pinfunction "C_C") (pintype "passive"))
      (node (ref "IC4") (pin "35") (pinfunction "OUT1_35") (pintype "output"))
      (node (ref "IC4") (pin "36") (pinfunction "OUT1_36") (pintype "output"))
      (node (ref "X1") (pin "1.1") (pinfunction "1_1.1") (pintype "bidirectional"))
      (node (ref "X1") (pin "1.2") (pinfunction "1_1.2") (pintype "bidirectional"))
    )
    (net (code "50") (name "Net-(D26--)") (class "Default")
      (node (ref "D26") (pin "C") (pinfunction "-_C") (pintype "passive"))
      (node (ref "OK4") (pin "7") (pinfunction "A_7") (pintype "passive"))
    )
    (net (code "51") (name "Net-(IC1A-1Q)") (class "Default")
      (node (ref "IC1") (pin "19") (pinfunction "1Q_19") (pintype "tri_state"))
      (node (ref "OK1") (pin "1") (pinfunction "A_1") (pintype "passive"))
    )
    (net (code "52") (name "Net-(IC1A-2Q)") (class "Default")
      (node (ref "IC1") (pin "18") (pinfunction "2Q_18") (pintype "tri_state"))
      (node (ref "OK1") (pin "3") (pinfunction "A_3") (pintype "passive"))
    )
    (net (code "53") (name "Net-(IC1A-3Q)") (class "Default")
      (node (ref "IC1") (pin "17") (pinfunction "3Q_17") (pintype "tri_state"))
      (node (ref "OK1") (pin "5") (pinfunction "A_5") (pintype "passive"))
    )
    (net (code "54") (name "Net-(IC1A-4Q)") (class "Default")
      (node (ref "IC1") (pin "16") (pinfunction "4Q_16") (pintype "tri_state"))
      (node (ref "OK1") (pin "7") (pinfunction "A_7") (pintype "passive"))
    )
    (net (code "55") (name "Net-(IC1A-5Q)") (class "Default")
      (node (ref "IC1") (pin "15") (pinfunction "5Q_15") (pintype "tri_state"))
      (node (ref "OK2") (pin "1") (pinfunction "A_1") (pintype "passive"))
    )
    (net (code "56") (name "Net-(IC1A-6Q)") (class "Default")
      (node (ref "IC1") (pin "14") (pinfunction "6Q_14") (pintype "tri_state"))
      (node (ref "OK2") (pin "3") (pinfunction "A_3") (pintype "passive"))
    )
    (net (code "57") (name "Net-(IC1A-7Q)") (class "Default")
      (node (ref "IC1") (pin "13") (pinfunction "7Q_13") (pintype "tri_state"))
      (node (ref "OK2") (pin "5") (pinfunction "A_5") (pintype "passive"))
    )
    (net (code "58") (name "Net-(IC1A-8Q)") (class "Default")
      (node (ref "IC1") (pin "12") (pinfunction "8Q_12") (pintype "tri_state"))
      (node (ref "OK2") (pin "7") (pinfunction "A_7") (pintype "passive"))
    )
    (net (code "59") (name "Net-(IC2A-1D)") (class "Default")
      (node (ref "IC2") (pin "2") (pinfunction "1D_2") (pintype "input"))
      (node (ref "OK4") (pin "10") (pinfunction "COL_10") (pintype "passive"))
      (node (ref "R3") (pin "2") (pinfunction "2_2") (pintype "passive"))
    )
    (net (code "60") (name "Net-(IC2A-2D)") (class "Default")
      (node (ref "IC2") (pin "3") (pinfunction "2D_3") (pintype "input"))
      (node (ref "OK4") (pin "12") (pinfunction "COL_12") (pintype "passive"))
      (node (ref "R4") (pin "2") (pinfunction "2_2") (pintype "passive"))
    )
    (net (code "61") (name "Net-(IC2A-3D)") (class "Default")
      (node (ref "IC2") (pin "4") (pinfunction "3D_4") (pintype "input"))
      (node (ref "OK4") (pin "14") (pinfunction "COL_14") (pintype "passive"))
      (node (ref "R5") (pin "2") (pinfunction "2_2") (pintype "passive"))
    )
    (net (code "62") (name "Net-(IC2A-4D)") (class "Default")
      (node (ref "IC2") (pin "5") (pinfunction "4D_5") (pintype "input"))
      (node (ref "OK4") (pin "16") (pinfunction "COL_16") (pintype "passive"))
      (node (ref "R6") (pin "2") (pinfunction "2_2") (pintype "passive"))
    )
    (net (code "63") (name "Net-(IC2A-5D)") (class "Default")
      (node (ref "IC2") (pin "6") (pinfunction "5D_6") (pintype "input"))
      (node (ref "OK3") (pin "10") (pinfunction "COL_10") (pintype "passive"))
      (node (ref "R7") (pin "2") (pinfunction "2_2") (pintype "passive"))
    )
    (net (code "64") (name "Net-(IC2A-6D)") (class "Default")
      (node (ref "IC2") (pin "7") (pinfunction "6D_7") (pintype "input"))
      (node (ref "OK3") (pin "12") (pinfunction "COL_12") (pintype "passive"))
      (node (ref "R8") (pin "2") (pinfunction "2_2") (pintype "passive"))
    )
    (net (code "65") (name "Net-(IC2A-7D)") (class "Default")
      (node (ref "IC2") (pin "8") (pinfunction "7D_8") (pintype "input"))
      (node (ref "OK3") (pin "14") (pinfunction "COL_14") (pintype "passive"))
      (node (ref "R9") (pin "2") (pinfunction "2_2") (pintype "passive"))
    )
    (net (code "66") (name "Net-(IC2A-8D)") (class "Default")
      (node (ref "IC2") (pin "9") (pinfunction "8D_9") (pintype "input"))
      (node (ref "OK3") (pin "16") (pinfunction "COL_16") (pintype "passive"))
      (node (ref "R10") (pin "2") (pinfunction "2_2") (pintype "passive"))
    )
    (net (code "67") (name "Net-(IC3A-1Q)") (class "Default")
      (node (ref "IC3") (pin "19") (pinfunction "1Q_19") (pintype "tri_state"))
      (node (ref "R19") (pin "1") (pinfunction "1_1") (pintype "passive"))
    )
    (net (code "68") (name "Net-(IC3A-2Q)") (class "Default")
      (node (ref "IC3") (pin "18") (pinfunction "2Q_18") (pintype "tri_state"))
      (node (ref "R20") (pin "1") (pinfunction "1_1") (pintype "passive"))
    )
    (net (code "69") (name "Net-(IC3A-3Q)") (class "Default")
      (node (ref "IC3") (pin "17") (pinfunction "3Q_17") (pintype "tri_state"))
      (node (ref "R21") (pin "1") (pinfunction "1_1") (pintype "passive"))
    )
    (net (code "70") (name "Net-(IC3A-4Q)") (class "Default")
      (node (ref "IC3") (pin "16") (pinfunction "4Q_16") (pintype "tri_state"))
      (node (ref "R22") (pin "1") (pinfunction "1_1") (pintype "passive"))
    )
    (net (code "71") (name "Net-(IC3A-5Q)") (class "Default")
      (node (ref "IC3") (pin "15") (pinfunction "5Q_15") (pintype "tri_state"))
      (node (ref "R23") (pin "1") (pinfunction "1_1") (pintype "passive"))
    )
    (net (code "72") (name "Net-(IC3A-6Q)") (class "Default")
      (node (ref "IC3") (pin "14") (pinfunction "6Q_14") (pintype "tri_state"))
      (node (ref "R24") (pin "1") (pinfunction "1_1") (pintype "passive"))
    )
    (net (code "73") (name "Net-(IC3A-7Q)") (class "Default")
      (node (ref "IC3") (pin "13") (pinfunction "7Q_13") (pintype "tri_state"))
      (node (ref "R25") (pin "1") (pinfunction "1_1") (pintype "passive"))
    )
    (net (code "74") (name "Net-(IC3A-8Q)") (class "Default")
      (node (ref "IC3") (pin "12") (pinfunction "8Q_12") (pintype "tri_state"))
      (node (ref "R26") (pin "1") (pinfunction "1_1") (pintype "passive"))
    )
    (net (code "75") (name "Net-(IC4-IN1)") (class "Default")
      (node (ref "IC4") (pin "6") (pinfunction "IN1_6") (pintype "input"))
      (node (ref "OK1") (pin "15") (pinfunction "EMIT_15") (pintype "passive"))
      (node (ref "RN1") (pin "2") (pinfunction "2_2") (pintype "passive"))
    )
    (net (code "76") (name "Net-(IC4-IN2)") (class "Default")
      (node (ref "IC4") (pin "7") (pinfunction "IN2_7") (pintype "input"))
      (node (ref "OK1") (pin "13") (pinfunction "EMIT_13") (pintype "passive"))
      (node (ref "RN1") (pin "3") (pinfunction "3_3") (pintype "passive"))
    )
    (net (code "77") (name "Net-(IC4-IN3)") (class "Default")
      (node (ref "IC4") (pin "8") (pinfunction "IN3_8") (pintype "input"))
      (node (ref "OK1") (pin "11") (pinfunction "EMIT_11") (pintype "passive"))
      (node (ref "RN1") (pin "4") (pinfunction "4_4") (pintype "passive"))
    )
    (net (code "78") (name "Net-(IC4-IN4)") (class "Default")
      (node (ref "IC4") (pin "9") (pinfunction "IN4_9") (pintype "input"))
      (node (ref "OK1") (pin "9") (pinfunction "EMIT_9") (pintype "passive"))
      (node (ref "RN1") (pin "5") (pinfunction "5_5") (pintype "passive"))
    )
    (net (code "79") (name "Net-(IC4-IN5)") (class "Default")
      (node (ref "IC4") (pin "10") (pinfunction "IN5_10") (pintype "input"))
      (node (ref "OK2") (pin "15") (pinfunction "EMIT_15") (pintype "passive"))
      (node (ref "RN1") (pin "6") (pinfunction "6_6") (pintype "passive"))
    )
    (net (code "80") (name "Net-(IC4-IN6)") (class "Default")
      (node (ref "IC4") (pin "11") (pinfunction "IN6_11") (pintype "input"))
      (node (ref "OK2") (pin "13") (pinfunction "EMIT_13") (pintype "passive"))
      (node (ref "RN1") (pin "7") (pinfunction "7_7") (pintype "passive"))
    )
    (net (code "81") (name "Net-(IC4-IN7)") (class "Default")
      (node (ref "IC4") (pin "12") (pinfunction "IN7_12") (pintype "input"))
      (node (ref "OK2") (pin "11") (pinfunction "EMIT_11") (pintype "passive"))
      (node (ref "RN1") (pin "8") (pinfunction "8_8") (pintype "passive"))
    )
    (net (code "82") (name "Net-(IC4-IN8)") (class "Default")
      (node (ref "IC4") (pin "13") (pinfunction "IN8_13") (pintype "input"))
      (node (ref "OK2") (pin "9") (pinfunction "EMIT_9") (pintype "passive"))
      (node (ref "RN1") (pin "9") (pinfunction "9_9") (pintype "passive"))
    )
    (net (code "83") (name "Net-(JP1-Pad2)") (class "Default")
      (node (ref "JP1") (pin "2") (pinfunction "2_2") (pintype "passive"))
      (node (ref "R50") (pin "1") (pinfunction "1_1") (pintype "passive"))
    )
    (net (code "84") (name "Net-(LED1-CG)") (class "Default")
      (node (ref "LED1") (pin "1") (pinfunction "CG_1") (pintype "passive"))
      (node (ref "R3") (pin "1") (pinfunction "1_1") (pintype "passive"))
    )
    (net (code "85") (name "Net-(LED1-CR)") (class "Default")
      (node (ref "LED1") (pin "3") (pinfunction "CR_3") (pintype "passive"))
      (node (ref "R19") (pin "2") (pinfunction "2_2") (pintype "passive"))
    )
    (net (code "86") (name "Net-(LED2-CG)") (class "Default")
      (node (ref "LED2") (pin "1") (pinfunction "CG_1") (pintype "passive"))
      (node (ref "R4") (pin "1") (pinfunction "1_1") (pintype "passive"))
    )
    (net (code "87") (name "Net-(LED2-CR)") (class "Default")
      (node (ref "LED2") (pin "3") (pinfunction "CR_3") (pintype "passive"))
      (node (ref "R20") (pin "2") (pinfunction "2_2") (pintype "passive"))
    )
    (net (code "88") (name "Net-(LED3-CG)") (class "Default")
      (node (ref "LED3") (pin "1") (pinfunction "CG_1") (pintype "passive"))
      (node (ref "R5") (pin "1") (pinfunction "1_1") (pintype "passive"))
    )
    (net (code "89") (name "Net-(LED3-CR)") (class "Default")
      (node (ref "LED3") (pin "3") (pinfunction "CR_3") (pintype "passive"))
      (node (ref "R21") (pin "2") (pinfunction "2_2") (pintype "passive"))
    )
    (net (code "90") (name "Net-(LED4-CG)") (class "Default")
      (node (ref "LED4") (pin "1") (pinfunction "CG_1") (pintype "passive"))
      (node (ref "R6") (pin "1") (pinfunction "1_1") (pintype "passive"))
    )
    (net (code "91") (name "Net-(LED4-CR)") (class "Default")
      (node (ref "LED4") (pin "3") (pinfunction "CR_3") (pintype "passive"))
      (node (ref "R22") (pin "2") (pinfunction "2_2") (pintype "passive"))
    )
    (net (code "92") (name "Net-(LED5-CG)") (class "Default")
      (node (ref "LED5") (pin "1") (pinfunction "CG_1") (pintype "passive"))
      (node (ref "R7") (pin "1") (pinfunction "1_1") (pintype "passive"))
    )
    (net (code "93") (name "Net-(LED5-CR)") (class "Default")
      (node (ref "LED5") (pin "3") (pinfunction "CR_3") (pintype "passive"))
      (node (ref "R23") (pin "2") (pinfunction "2_2") (pintype "passive"))
    )
    (net (code "94") (name "Net-(LED6-CG)") (class "Default")
      (node (ref "LED6") (pin "1") (pinfunction "CG_1") (pintype "passive"))
      (node (ref "R8") (pin "1") (pinfunction "1_1") (pintype "passive"))
    )
    (net (code "95") (name "Net-(LED6-CR)") (class "Default")
      (node (ref "LED6") (pin "3") (pinfunction "CR_3") (pintype "passive"))
      (node (ref "R24") (pin "2") (pinfunction "2_2") (pintype "passive"))
    )
    (net (code "96") (name "Net-(LED7-CG)") (class "Default")
      (node (ref "LED7") (pin "1") (pinfunction "CG_1") (pintype "passive"))
      (node (ref "R9") (pin "1") (pinfunction "1_1") (pintype "passive"))
    )
    (net (code "97") (name "Net-(LED7-CR)") (class "Default")
      (node (ref "LED7") (pin "3") (pinfunction "CR_3") (pintype "passive"))
      (node (ref "R25") (pin "2") (pinfunction "2_2") (pintype "passive"))
    )
    (net (code "98") (name "Net-(LED8-CG)") (class "Default")
      (node (ref "LED8") (pin "1") (pinfunction "CG_1") (pintype "passive"))
      (node (ref "R10") (pin "1") (pinfunction "1_1") (pintype "passive"))
    )
    (net (code "99") (name "Net-(LED8-CR)") (class "Default")
      (node (ref "LED8") (pin "3") (pinfunction "CR_3") (pintype "passive"))
      (node (ref "R26") (pin "2") (pinfunction "2_2") (pintype "passive"))
    )
    (net (code "100") (name "Net-(OK1A-C)") (class "Default")
      (node (ref "OK1") (pin "2") (pinfunction "C_2") (pintype "passive"))
      (node (ref "R11") (pin "2") (pinfunction "2_2") (pintype "passive"))
    )
    (net (code "101") (name "Net-(OK1B-C)") (class "Default")
      (node (ref "OK1") (pin "4") (pinfunction "C_4") (pintype "passive"))
      (node (ref "R12") (pin "2") (pinfunction "2_2") (pintype "passive"))
    )
    (net (code "102") (name "Net-(OK1C-C)") (class "Default")
      (node (ref "OK1") (pin "6") (pinfunction "C_6") (pintype "passive"))
      (node (ref "R13") (pin "2") (pinfunction "2_2") (pintype "passive"))
    )
    (net (code "103") (name "Net-(OK1D-C)") (class "Default")
      (node (ref "OK1") (pin "8") (pinfunction "C_8") (pintype "passive"))
      (node (ref "R14") (pin "2") (pinfunction "2_2") (pintype "passive"))
    )
    (net (code "104") (name "Net-(OK2A-C)") (class "Default")
      (node (ref "OK2") (pin "2") (pinfunction "C_2") (pintype "passive"))
      (node (ref "R15") (pin "2") (pinfunction "2_2") (pintype "passive"))
    )
    (net (code "105") (name "Net-(OK2B-C)") (class "Default")
      (node (ref "OK2") (pin "4") (pinfunction "C_4") (pintype "passive"))
      (node (ref "R16") (pin "2") (pinfunction "2_2") (pintype "passive"))
    )
    (net (code "106") (name "Net-(OK2C-C)") (class "Default")
      (node (ref "OK2") (pin "6") (pinfunction "C_6") (pintype "passive"))
      (node (ref "R17") (pin "2") (pinfunction "2_2") (pintype "passive"))
    )
    (net (code "107") (name "Net-(OK2D-C)") (class "Default")
      (node (ref "OK2") (pin "8") (pinfunction "C_8") (pintype "passive"))
      (node (ref "R18") (pin "2") (pinfunction "2_2") (pintype "passive"))
    )
    (net (code "108") (name "Net-(OK3A-C)") (class "Default")
      (node (ref "OK3") (pin "2") (pinfunction "C_2") (pintype "passive"))
      (node (ref "RN2") (pin "2") (pinfunction "2_2") (pintype "passive"))
    )
    (net (code "109") (name "Net-(OK3B-C)") (class "Default")
      (node (ref "OK3") (pin "4") (pinfunction "C_4") (pintype "passive"))
      (node (ref "RN2") (pin "3") (pinfunction "3_3") (pintype "passive"))
    )
    (net (code "110") (name "Net-(OK3C-C)") (class "Default")
      (node (ref "OK3") (pin "6") (pinfunction "C_6") (pintype "passive"))
      (node (ref "RN2") (pin "4") (pinfunction "4_4") (pintype "passive"))
    )
    (net (code "111") (name "Net-(OK3D-C)") (class "Default")
      (node (ref "OK3") (pin "8") (pinfunction "C_8") (pintype "passive"))
      (node (ref "RN2") (pin "5") (pinfunction "5_5") (pintype "passive"))
    )
    (net (code "112") (name "Net-(OK4A-C)") (class "Default")
      (node (ref "OK4") (pin "2") (pinfunction "C_2") (pintype "passive"))
      (node (ref "RN2") (pin "6") (pinfunction "6_6") (pintype "passive"))
    )
    (net (code "113") (name "Net-(OK4B-C)") (class "Default")
      (node (ref "OK4") (pin "4") (pinfunction "C_4") (pintype "passive"))
      (node (ref "RN2") (pin "7") (pinfunction "7_7") (pintype "passive"))
    )
    (net (code "114") (name "Net-(OK4C-C)") (class "Default")
      (node (ref "OK4") (pin "6") (pinfunction "C_6") (pintype "passive"))
      (node (ref "RN2") (pin "8") (pinfunction "8_8") (pintype "passive"))
    )
    (net (code "115") (name "Net-(OK4D-C)") (class "Default")
      (node (ref "OK4") (pin "8") (pinfunction "C_8") (pintype "passive"))
      (node (ref "RN2") (pin "9") (pinfunction "9_9") (pintype "passive"))
    )
    (net (code "116") (name "Net-(Q1-D)") (class "Default")
      (node (ref "D10") (pin "C") (pinfunction "C_C") (pintype "passive"))
      (node (ref "Q1") (pin "2") (pinfunction "D_2") (pintype "passive"))
      (node (ref "R2") (pin "1") (pinfunction "1_1") (pintype "passive"))
    )
    (net (code "117") (name "Net-(Q1-G)") (class "Default")
      (node (ref "D9") (pin "A") (pinfunction "A_A") (pintype "passive"))
      (node (ref "Q1") (pin "1") (pinfunction "G_1") (pintype "passive"))
      (node (ref "R1") (pin "2") (pinfunction "2_2") (pintype "passive"))
    )
    (net (code "118") (name "Net-(Q2-OUT)") (class "Default")
      (node (ref "Q2") (pin "3") (pinfunction "OUT_3") (pintype "output"))
      (node (ref "U1") (pin "7") (pinfunction "PB6(XTAL1/TOSC1)_7") (pintype "bidirectional"))
    )
    (net (code "119") (name "Net-(R2-Pad2)") (class "Default")
      (node (ref "R2") (pin "2") (pinfunction "2_2") (pintype "passive"))
      (node (ref "X5") (pin "1.1") (pinfunction "1_1.1") (pintype "bidirectional"))
      (node (ref "X5") (pin "1.2") (pinfunction "1_1.2") (pintype "bidirectional"))
    )
    (net (code "120") (name "unconnected-(IC4-DIAG-Pad20)") (class "Default")
      (node (ref "IC4") (pin "20") (pinfunction "DIAG_20") (pintype "output"))
    )
    (net (code "121") (name "unconnected-(Q2-TS-Pad1)") (class "Default")
      (node (ref "Q2") (pin "1") (pinfunction "TS_1") (pintype "passive"))
    )
    (net (code "122") (name "unconnected-(U1-PB0(ICP)-Pad12)") (class "Default")
      (node (ref "U1") (pin "12") (pinfunction "PB0(ICP)_12") (pintype "bidirectional"))
    )
    (net (code "123") (name "unconnected-(U1-PB1(OC1A)-Pad13)") (class "Default")
      (node (ref "U1") (pin "13") (pinfunction "PB1(OC1A)_13") (pintype "bidirectional"))
    )
    (net (code "124") (name "unconnected-(U1-PB2(SS{slash}OC1B)-Pad14)") (class "Default")
      (node (ref "U1") (pin "14") (pinfunction "PB2(SS/OC1B)_14") (pintype "bidirectional"))
    )
    (net (code "125") (name "unconnected-(U1-PB7(XTAL2{slash}TOSC2)-Pad8)") (class "Default")
      (node (ref "U1") (pin "8") (pinfunction "PB7(XTAL2/TOSC2)_8") (pintype "bidirectional"))
    )
  )
)
